# LC_MATCH_1.net
KiCad netlist of a schematic drawn in Altium Designer
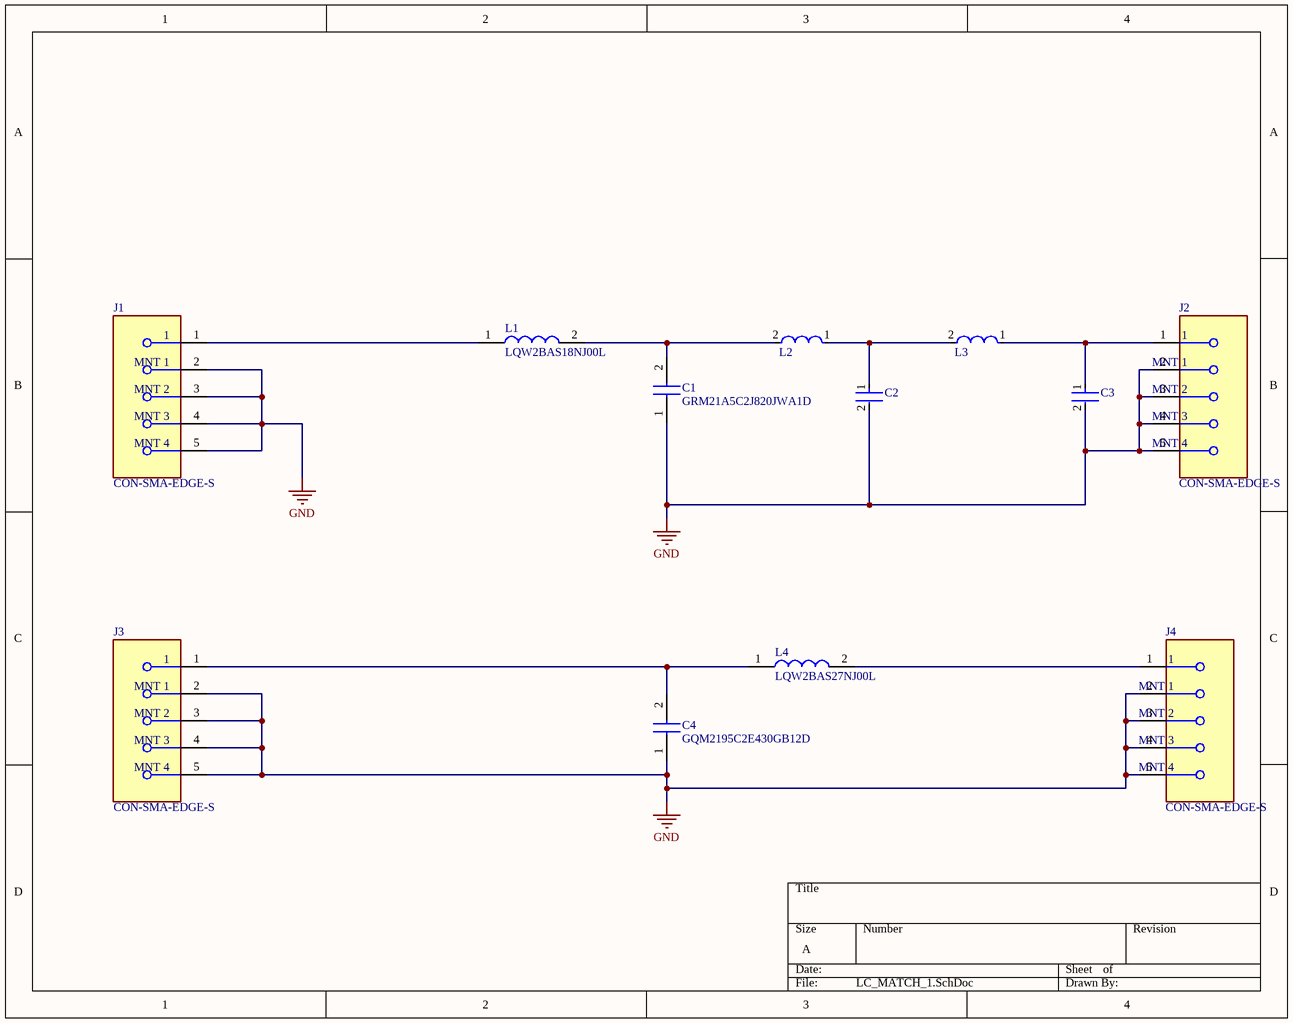
[diagram p0: LC_MATCH_1.SchDoc]

(export (version "E")
  (design (tool "Eeschema 10.0.6"))
  (components
    (comp (ref "C1")
      (value "GRM21A5C2J820JWA1D")
      (footprint "SamacSys:GRM21x")
      (description "Capacitor")
      (libsource (lib "*") (part "GRM21A5C2J820JWA1D"))
    )
    (comp (ref "C2")
      (value "GQM2195C2E430GB12D")
      (footprint "FP-GRM21A-0_2-MFG")
      (description "Chip Multilayer Ceramic Capacitors for General Purpose, 0805, 1000pF, C0G, 30ppm/°C, 1%, 250V")
      (libsource (lib "Altium Content Vault") (part "02cd4be3c70576c341d710602a673aa"))
    )
    (comp (ref "C3")
      (value "GQM2195C2E300GB12D")
      (footprint "FP-GRM21A-0_2-MFG")
      (description "Chip Multilayer Ceramic Capacitors for General Purpose, 0805, 1000pF, C0G, 30ppm/°C, 1%, 250V")
      (libsource (lib "Altium Content Vault") (part "02cd4be3c70576c341d710602a673aa"))
    )
    (comp (ref "C4")
      (value "GQM2195C2E430GB12D")
      (footprint "SamacSys:GQM2195C2E100GB12D")
      (description "Capacitor")
      (libsource (lib "*") (part "GQM2195C2E430GB12D"))
    )
    (comp (ref "J1")
      (value "CON-SMA-EDGE-S")
      (footprint "FP-CON-SMA-EDGE-S-MFG")
      (description "CONN SMA JACK STR EDGE MNT")
      (fields
        (field (name "OCTOPART") "https://octopart.com/con-sma-edge-s-rf+solutions-70967450")
        (field (name "MANUFACTURER") "RF Solutions Ltd.")
      )
      (libsource (lib "") (part "a163d97a771fcdd2fd1f1a9264c171f_1"))
    )
    (comp (ref "J2")
      (value "CON-SMA-EDGE-S")
      (footprint "FP-CON-SMA-EDGE-S-MFG")
      (description "CONN SMA JACK STR EDGE MNT")
      (fields
        (field (name "OCTOPART") "https://octopart.com/con-sma-edge-s-rf+solutions-70967450")
        (field (name "MANUFACTURER") "RF Solutions Ltd.")
      )
      (libsource (lib "Altium Content Vault") (part "a163d97a771fcdd2fd1f1a9264c171f"))
    )
    (comp (ref "J3")
      (value "CON-SMA-EDGE-S")
      (footprint "FP-CON-SMA-EDGE-S-MFG")
      (description "CONN SMA JACK STR EDGE MNT")
      (fields
        (field (name "OCTOPART") "https://octopart.com/con-sma-edge-s-rf+solutions-70967450")
        (field (name "MANUFACTURER") "RF Solutions Ltd.")
      )
      (libsource (lib "") (part "a163d97a771fcdd2fd1f1a9264c171f_1"))
    )
    (comp (ref "J4")
      (value "CON-SMA-EDGE-S")
      (footprint "FP-CON-SMA-EDGE-S-MFG")
      (description "CONN SMA JACK STR EDGE MNT")
      (fields
        (field (name "OCTOPART") "https://octopart.com/con-sma-edge-s-rf+solutions-70967450")
        (field (name "MANUFACTURER") "RF Solutions Ltd.")
      )
      (libsource (lib "Altium Content Vault") (part "a163d97a771fcdd2fd1f1a9264c171f"))
    )
    (comp (ref "L1")
      (value "LQW2BAS18NJ00L")
      (footprint "SamacSys:LQW2BAN11NG00L")
      (description "Inductor")
      (fields (field (name "MOUSER PART NUMBER") "81-LQW2BAS18NJ00L"))
      (libsource (lib "*") (part "LQW2BAS18NJ00L"))
    )
    (comp (ref "L2")
      (value "LQW2BAS56NG00L")
      (footprint "FP-LQW2BAN_00-MFG")
      (description "Wire Wound RF Inductor 56nH ±2% 500mA 0.34Ω 0805 (2015)")
      (fields (field (name "TOLERANCE") "2%"))
      (libsource (lib "Altium Content Vault") (part "725321dda6339637d4d059423bc1c3c"))
    )
    (comp (ref "L3")
      (value "LQW2BAS56NG00L")
      (footprint "FP-LQW2BAN_00-MFG")
      (description "Wire Wound RF Inductor 56nH ±2% 500mA 0.34Ω 0805 (2015)")
      (fields (field (name "TOLERANCE") "2%"))
      (libsource (lib "Altium Content Vault") (part "725321dda6339637d4d059423bc1c3c"))
    )
    (comp (ref "L4")
      (value "LQW2BAS27NJ00L")
      (footprint "SamacSys:LQW2BAN11NG00L")
      (description "Inductor")
      (fields (field (name "MOUSER PART NUMBER") "81-LQW2BAS27NJ00L"))
      (libsource (lib "*") (part "LQW2BAS27NJ00L"))
    )
  )
  (nets
    (net (code "1") (name "GND") (class "Default")
      (node (ref "C1") (pin "1") (pinfunction "1_1") (pintype "passive"))
      (node (ref "C2") (pin "2") (pinfunction "2_2") (pintype "passive"))
      (node (ref "C3") (pin "2") (pinfunction "2_2") (pintype "passive"))
      (node (ref "C4") (pin "1") (pinfunction "1_1") (pintype "passive"))
      (node (ref "J1") (pin "2") (pinfunction "MNT_1_2") (pintype "passive"))
      (node (ref "J1") (pin "3") (pinfunction "MNT_2_3") (pintype "passive"))
      (node (ref "J1") (pin "4") (pinfunction "MNT_3_4") (pintype "passive"))
      (node (ref "J1") (pin "5") (pinfunction "MNT_4_5") (pintype "passive"))
      (node (ref "J2") (pin "2") (pinfunction "MNT_1_2") (pintype "passive"))
      (node (ref "J2") (pin "3") (pinfunction "MNT_2_3") (pintype "passive"))
      (node (ref "J2") (pin "4") (pinfunction "MNT_3_4") (pintype "passive"))
      (node (ref "J2") (pin "5") (pinfunction "MNT_4_5") (pintype "passive"))
      (node (ref "J3") (pin "2") (pinfunction "MNT_1_2") (pintype "passive"))
      (node (ref "J3") (pin "3") (pinfunction "MNT_2_3") (pintype "passive"))
      (node (ref "J3") (pin "4") (pinfunction "MNT_3_4") (pintype "passive"))
      (node (ref "J3") (pin "5") (pinfunction "MNT_4_5") (pintype "passive"))
      (node (ref "J4") (pin "2") (pinfunction "MNT_1_2") (pintype "passive"))
      (node (ref "J4") (pin "3") (pinfunction "MNT_2_3") (pintype "passive"))
      (node (ref "J4") (pin "4") (pinfunction "MNT_3_4") (pintype "passive"))
      (node (ref "J4") (pin "5") (pinfunction "MNT_4_5") (pintype "passive"))
    )
    (net (code "2") (name "Net-(C1-Pad2)") (class "Default")
      (node (ref "C1") (pin "2") (pinfunction "2_2") (pintype "passive"))
      (node (ref "L1") (pin "2") (pinfunction "2_2") (pintype "passive"))
      (node (ref "L2") (pin "2") (pinfunction "2_2") (pintype "passive"))
    )
    (net (code "3") (name "Net-(C2-Pad1)") (class "Default")
      (node (ref "C2") (pin "1") (pinfunction "1_1") (pintype "passive"))
      (node (ref "L2") (pin "1") (pinfunction "1_1") (pintype "passive"))
      (node (ref "L3") (pin "2") (pinfunction "2_2") (pintype "passive"))
    )
    (net (code "4") (name "Net-(C3-Pad1)") (class "Default")
      (node (ref "C3") (pin "1") (pinfunction "1_1") (pintype "passive"))
      (node (ref "J2") (pin "1") (pinfunction "1_1") (pintype "passive"))
      (node (ref "L3") (pin "1") (pinfunction "1_1") (pintype "passive"))
    )
    (net (code "5") (name "Net-(C4-Pad2)") (class "Default")
      (node (ref "C4") (pin "2") (pinfunction "2_2") (pintype "passive"))
      (node (ref "J3") (pin "1") (pinfunction "1_1") (pintype "passive"))
      (node (ref "L4") (pin "1") (pinfunction "1_1") (pintype "passive"))
    )
    (net (code "6") (name "Net-(J1-Pad1)") (class "Default")
      (node (ref "J1") (pin "1") (pinfunction "1_1") (pintype "passive"))
      (node (ref "L1") (pin "1") (pinfunction "1_1") (pintype "passive"))
    )
    (net (code "7") (name "Net-(J4-Pad1)") (class "Default")
      (node (ref "J4") (pin "1") (pinfunction "1_1") (pintype "passive"))
      (node (ref "L4") (pin "2") (pinfunction "2_2") (pintype "passive"))
    )
  )
)
